# zero_board.net
KiCad netlist of a schematic drawn in EAGLE
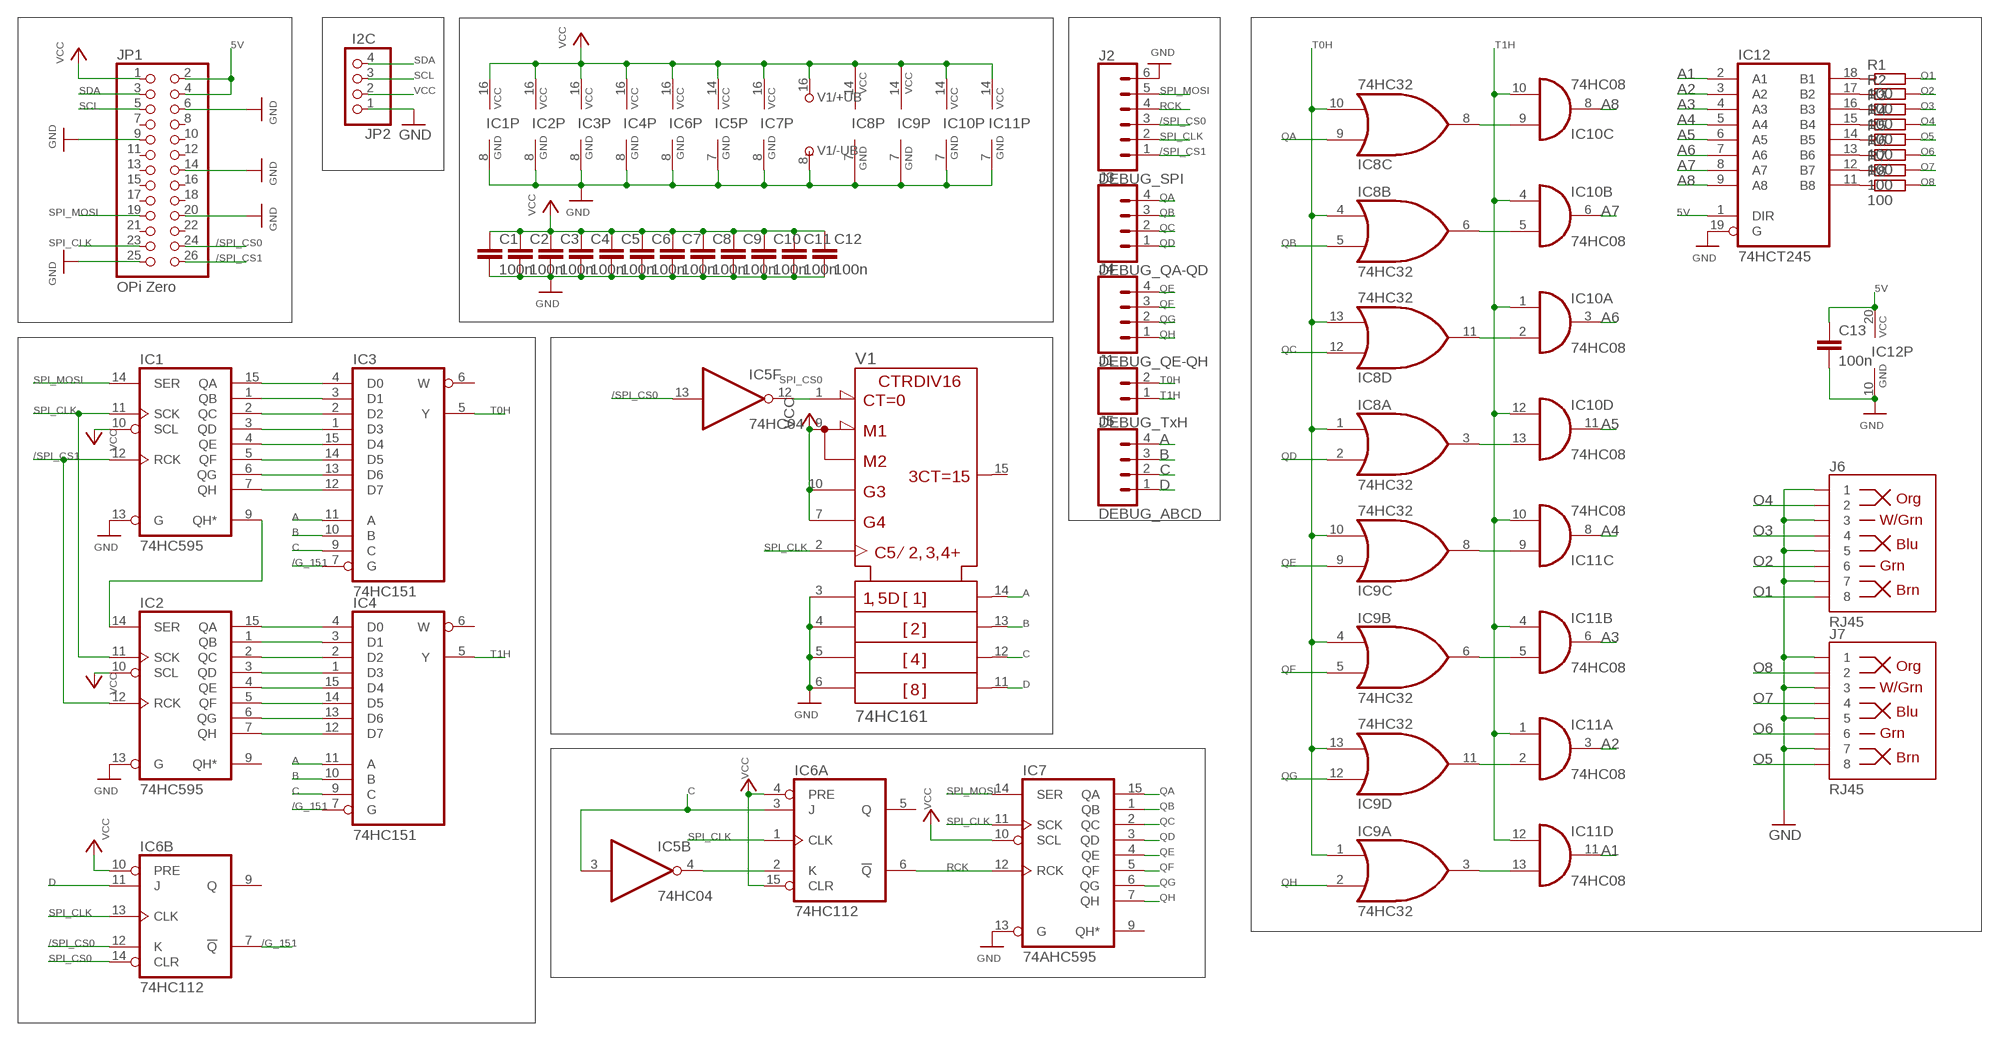
[diagram p0: schematic, sheet 1]

(export (version "E")
  (design (tool "Eeschema 10.0.6"))
  (components
    (comp (ref "C1")
      (value "100n")
      (footprint "eagle-import:C050-024X044")
      (libsource (lib "eagle-import") (part "C-EU050-024X044"))
    )
    (comp (ref "C2")
      (value "100n")
      (footprint "eagle-import:C050-024X044")
      (libsource (lib "eagle-import") (part "C-EU050-024X044"))
    )
    (comp (ref "C3")
      (value "100n")
      (footprint "eagle-import:C050-024X044")
      (libsource (lib "eagle-import") (part "C-EU050-024X044"))
    )
    (comp (ref "C4")
      (value "100n")
      (footprint "eagle-import:C050-024X044")
      (libsource (lib "eagle-import") (part "C-EU050-024X044"))
    )
    (comp (ref "C5")
      (value "100n")
      (footprint "eagle-import:C050-024X044")
      (libsource (lib "eagle-import") (part "C-EU050-024X044"))
    )
    (comp (ref "C6")
      (value "100n")
      (footprint "eagle-import:C050-024X044")
      (libsource (lib "eagle-import") (part "C-EU050-024X044"))
    )
    (comp (ref "C7")
      (value "100n")
      (footprint "eagle-import:C050-024X044")
      (libsource (lib "eagle-import") (part "C-EU050-024X044"))
    )
    (comp (ref "C8")
      (value "100n")
      (footprint "eagle-import:C050-024X044")
      (libsource (lib "eagle-import") (part "C-EU050-024X044"))
    )
    (comp (ref "C9")
      (value "100n")
      (footprint "eagle-import:C050-024X044")
      (libsource (lib "eagle-import") (part "C-EU050-024X044"))
    )
    (comp (ref "C10")
      (value "100n")
      (footprint "eagle-import:C050-024X044")
      (libsource (lib "eagle-import") (part "C-EU050-024X044"))
    )
    (comp (ref "C11")
      (value "100n")
      (footprint "eagle-import:C050-024X044")
      (libsource (lib "eagle-import") (part "C-EU050-024X044"))
    )
    (comp (ref "C12")
      (value "100n")
      (footprint "eagle-import:C050-024X044")
      (libsource (lib "eagle-import") (part "C-EU050-024X044"))
    )
    (comp (ref "C13")
      (value "100n")
      (footprint "eagle-import:C050-024X044")
      (libsource (lib "eagle-import") (part "C-EU050-024X044"))
    )
    (comp (ref "IC1")
      (value "74HC595")
      (footprint "eagle-import:DIL16")
      (libsource (lib "eagle-import") (part "74595NHC"))
    )
    (comp (ref "IC2")
      (value "74HC595")
      (footprint "eagle-import:DIL16")
      (libsource (lib "eagle-import") (part "74595NHC"))
    )
    (comp (ref "IC3")
      (value "74HC151")
      (footprint "eagle-import:DIL16")
      (libsource (lib "eagle-import") (part "74151NHC"))
    )
    (comp (ref "IC4")
      (value "74HC151")
      (footprint "eagle-import:DIL16")
      (libsource (lib "eagle-import") (part "74151NHC"))
    )
    (comp (ref "IC5")
      (value "74HC04")
      (footprint "eagle-import:DIL14")
      (libsource (lib "eagle-import") (part "7404NHC"))
    )
    (comp (ref "IC6")
      (value "74HC112")
      (footprint "eagle-import:DIL16")
      (libsource (lib "eagle-import") (part "74112NHC"))
    )
    (comp (ref "IC7")
      (value "74AHC595")
      (footprint "eagle-import:SO16")
      (libsource (lib "eagle-import") (part "74595DHC"))
    )
    (comp (ref "IC8")
      (value "74HC32")
      (footprint "eagle-import:DIL14")
      (libsource (lib "eagle-import") (part "7432NLS"))
    )
    (comp (ref "IC9")
      (value "74HC32")
      (footprint "eagle-import:DIL14")
      (libsource (lib "eagle-import") (part "7432NLS"))
    )
    (comp (ref "IC10")
      (value "74HC08")
      (footprint "eagle-import:DIL14")
      (libsource (lib "eagle-import") (part "7408NAS"))
    )
    (comp (ref "IC11")
      (value "74HC08")
      (footprint "eagle-import:DIL14")
      (libsource (lib "eagle-import") (part "7408NAS"))
    )
    (comp (ref "IC12")
      (value "74HCT245")
      (footprint "eagle-import:DIL20")
      (libsource (lib "eagle-import") (part "74245NACT"))
    )
    (comp (ref "J1")
      (value "DEBUG_TxH")
      (footprint "eagle-import:1X02")
      (libsource (lib "eagle-import") (part "CONN_02"))
    )
    (comp (ref "J2")
      (value "DEBUG_SPI")
      (footprint "eagle-import:1X06_LOCK")
      (libsource (lib "eagle-import") (part "CONN_06LOCK"))
    )
    (comp (ref "J3")
      (value "DEBUG_QA-QD")
      (footprint "eagle-import:1X04_LOCK")
      (libsource (lib "eagle-import") (part "CONN_04LOCK"))
    )
    (comp (ref "J4")
      (value "DEBUG_QE-QH")
      (footprint "eagle-import:1X04_LOCK")
      (libsource (lib "eagle-import") (part "CONN_04LOCK"))
    )
    (comp (ref "J5")
      (value "DEBUG_ABCD")
      (footprint "eagle-import:1X04_LOCK")
      (libsource (lib "eagle-import") (part "CONN_04LOCK"))
    )
    (comp (ref "J6")
      (value "RJ45")
      (footprint "eagle-import:RJ45-8")
      (libsource (lib "eagle-import") (part "RJ45-8"))
    )
    (comp (ref "J7")
      (value "RJ45")
      (footprint "eagle-import:RJ45-8")
      (libsource (lib "eagle-import") (part "RJ45-8"))
    )
    (comp (ref "JP1")
      (value "OPi Zero")
      (footprint "eagle-import:2X13")
      (libsource (lib "eagle-import") (part "PINHD-2X13"))
    )
    (comp (ref "JP2")
      (value "I2C")
      (footprint "eagle-import:1X04")
      (libsource (lib "eagle-import") (part "PINHD-1X4"))
    )
    (comp (ref "R1")
      (value "100")
      (footprint "eagle-import:0204_5")
      (libsource (lib "eagle-import") (part "R-EU_0204/5"))
    )
    (comp (ref "R2")
      (value "100")
      (footprint "eagle-import:0204_5")
      (libsource (lib "eagle-import") (part "R-EU_0204/5"))
    )
    (comp (ref "R3")
      (value "100")
      (footprint "eagle-import:0204_5")
      (libsource (lib "eagle-import") (part "R-EU_0204/5"))
    )
    (comp (ref "R4")
      (value "100")
      (footprint "eagle-import:0204_5")
      (libsource (lib "eagle-import") (part "R-EU_0204/5"))
    )
    (comp (ref "R5")
      (value "100")
      (footprint "eagle-import:0204_5")
      (libsource (lib "eagle-import") (part "R-EU_0204/5"))
    )
    (comp (ref "R6")
      (value "100")
      (footprint "eagle-import:0204_5")
      (libsource (lib "eagle-import") (part "R-EU_0204/5"))
    )
    (comp (ref "R7")
      (value "100")
      (footprint "eagle-import:0204_5")
      (libsource (lib "eagle-import") (part "R-EU_0204/5"))
    )
    (comp (ref "R8")
      (value "100")
      (footprint "eagle-import:0204_5")
      (libsource (lib "eagle-import") (part "R-EU_0204/5"))
    )
    (comp (ref "V1")
      (value "74HC161")
      (footprint "eagle-import:DIL16")
      (libsource (lib "eagle-import") (part "74161N"))
    )
  )
  (nets
    (net (code "1") (name "/5V") (class "Default")
      (node (ref "C13") (pin "1") (pinfunction "1_1") (pintype "passive"))
      (node (ref "IC12") (pin "1") (pinfunction "DIR_1") (pintype "input"))
      (node (ref "IC12") (pin "20") (pinfunction "VCC_20") (pintype "power_in"))
      (node (ref "JP1") (pin "2") (pinfunction "2_2") (pintype "passive"))
      (node (ref "JP1") (pin "4") (pinfunction "4_4") (pintype "passive"))
    )
    (net (code "2") (name "/A") (class "Default")
      (node (ref "IC3") (pin "11") (pinfunction "A_11") (pintype "input"))
      (node (ref "IC4") (pin "11") (pinfunction "A_11") (pintype "input"))
      (node (ref "J5") (pin "4") (pinfunction "4_4") (pintype "passive"))
      (node (ref "V1") (pin "14") (pinfunction "QA_14") (pintype "output"))
    )
    (net (code "3") (name "/A1") (class "Default")
      (node (ref "IC11") (pin "11") (pinfunction "O_11") (pintype "output"))
      (node (ref "IC12") (pin "2") (pinfunction "A1_2") (pintype "bidirectional"))
    )
    (net (code "4") (name "/A2") (class "Default")
      (node (ref "IC11") (pin "3") (pinfunction "O_3") (pintype "output"))
      (node (ref "IC12") (pin "3") (pinfunction "A2_3") (pintype "bidirectional"))
    )
    (net (code "5") (name "/A3") (class "Default")
      (node (ref "IC11") (pin "6") (pinfunction "O_6") (pintype "output"))
      (node (ref "IC12") (pin "4") (pinfunction "A3_4") (pintype "bidirectional"))
    )
    (net (code "6") (name "/A4") (class "Default")
      (node (ref "IC11") (pin "8") (pinfunction "O_8") (pintype "output"))
      (node (ref "IC12") (pin "5") (pinfunction "A4_5") (pintype "bidirectional"))
    )
    (net (code "7") (name "/A5") (class "Default")
      (node (ref "IC10") (pin "11") (pinfunction "O_11") (pintype "output"))
      (node (ref "IC12") (pin "6") (pinfunction "A5_6") (pintype "bidirectional"))
    )
    (net (code "8") (name "/A6") (class "Default")
      (node (ref "IC10") (pin "3") (pinfunction "O_3") (pintype "output"))
      (node (ref "IC12") (pin "7") (pinfunction "A6_7") (pintype "bidirectional"))
    )
    (net (code "9") (name "/A7") (class "Default")
      (node (ref "IC10") (pin "6") (pinfunction "O_6") (pintype "output"))
      (node (ref "IC12") (pin "8") (pinfunction "A7_8") (pintype "bidirectional"))
    )
    (net (code "10") (name "/A8") (class "Default")
      (node (ref "IC10") (pin "8") (pinfunction "O_8") (pintype "output"))
      (node (ref "IC12") (pin "9") (pinfunction "A8_9") (pintype "bidirectional"))
    )
    (net (code "11") (name "/B") (class "Default")
      (node (ref "IC3") (pin "10") (pinfunction "B_10") (pintype "input"))
      (node (ref "IC4") (pin "10") (pinfunction "B_10") (pintype "input"))
      (node (ref "J5") (pin "3") (pinfunction "3_3") (pintype "passive"))
      (node (ref "V1") (pin "13") (pinfunction "QB_13") (pintype "output"))
    )
    (net (code "12") (name "/C") (class "Default")
      (node (ref "IC3") (pin "9") (pinfunction "C_9") (pintype "input"))
      (node (ref "IC4") (pin "9") (pinfunction "C_9") (pintype "input"))
      (node (ref "IC5") (pin "3") (pinfunction "I_3") (pintype "input"))
      (node (ref "IC6") (pin "3") (pinfunction "J_3") (pintype "input"))
      (node (ref "J5") (pin "2") (pinfunction "2_2") (pintype "passive"))
      (node (ref "V1") (pin "12") (pinfunction "QC_12") (pintype "output"))
    )
    (net (code "13") (name "/D") (class "Default")
      (node (ref "IC6") (pin "11") (pinfunction "J_11") (pintype "input"))
      (node (ref "J5") (pin "1") (pinfunction "1_1") (pintype "passive"))
      (node (ref "V1") (pin "11") (pinfunction "QD_11") (pintype "output"))
    )
    (net (code "14") (name "/O1") (class "Default")
      (node (ref "J6") (pin "8") (pinfunction "8_8") (pintype "bidirectional"))
      (node (ref "R1") (pin "2") (pinfunction "2_2") (pintype "passive"))
    )
    (net (code "15") (name "/O2") (class "Default")
      (node (ref "J6") (pin "6") (pinfunction "6_6") (pintype "bidirectional"))
      (node (ref "R2") (pin "2") (pinfunction "2_2") (pintype "passive"))
    )
    (net (code "16") (name "/O3") (class "Default")
      (node (ref "J6") (pin "4") (pinfunction "4_4") (pintype "bidirectional"))
      (node (ref "R3") (pin "2") (pinfunction "2_2") (pintype "passive"))
    )
    (net (code "17") (name "/O4") (class "Default")
      (node (ref "J6") (pin "2") (pinfunction "2_2") (pintype "bidirectional"))
      (node (ref "R4") (pin "2") (pinfunction "2_2") (pintype "passive"))
    )
    (net (code "18") (name "/O5") (class "Default")
      (node (ref "J7") (pin "8") (pinfunction "8_8") (pintype "bidirectional"))
      (node (ref "R5") (pin "2") (pinfunction "2_2") (pintype "passive"))
    )
    (net (code "19") (name "/O6") (class "Default")
      (node (ref "J7") (pin "6") (pinfunction "6_6") (pintype "bidirectional"))
      (node (ref "R6") (pin "2") (pinfunction "2_2") (pintype "passive"))
    )
    (net (code "20") (name "/O7") (class "Default")
      (node (ref "J7") (pin "4") (pinfunction "4_4") (pintype "bidirectional"))
      (node (ref "R7") (pin "2") (pinfunction "2_2") (pintype "passive"))
    )
    (net (code "21") (name "/O8") (class "Default")
      (node (ref "J7") (pin "2") (pinfunction "2_2") (pintype "bidirectional"))
      (node (ref "R8") (pin "2") (pinfunction "2_2") (pintype "passive"))
    )
    (net (code "22") (name "/QA") (class "Default")
      (node (ref "IC7") (pin "15") (pinfunction "QA_15") (pintype "tri_state"))
      (node (ref "IC8") (pin "9") (pinfunction "I0_9") (pintype "input"))
      (node (ref "J3") (pin "4") (pinfunction "4_4") (pintype "passive"))
    )
    (net (code "23") (name "/QB") (class "Default")
      (node (ref "IC7") (pin "1") (pinfunction "QB_1") (pintype "tri_state"))
      (node (ref "IC8") (pin "5") (pinfunction "I1_5") (pintype "input"))
      (node (ref "J3") (pin "3") (pinfunction "3_3") (pintype "passive"))
    )
    (net (code "24") (name "/QC") (class "Default")
      (node (ref "IC7") (pin "2") (pinfunction "QC_2") (pintype "tri_state"))
      (node (ref "IC8") (pin "12") (pinfunction "I0_12") (pintype "input"))
      (node (ref "J3") (pin "2") (pinfunction "2_2") (pintype "passive"))
    )
    (net (code "25") (name "/QD") (class "Default")
      (node (ref "IC7") (pin "3") (pinfunction "QD_3") (pintype "tri_state"))
      (node (ref "IC8") (pin "2") (pinfunction "I1_2") (pintype "input"))
      (node (ref "J3") (pin "1") (pinfunction "1_1") (pintype "passive"))
    )
    (net (code "26") (name "/QE") (class "Default")
      (node (ref "IC7") (pin "4") (pinfunction "QE_4") (pintype "tri_state"))
      (node (ref "IC9") (pin "9") (pinfunction "I0_9") (pintype "input"))
      (node (ref "J4") (pin "4") (pinfunction "4_4") (pintype "passive"))
    )
    (net (code "27") (name "/QF") (class "Default")
      (node (ref "IC7") (pin "5") (pinfunction "QF_5") (pintype "tri_state"))
      (node (ref "IC9") (pin "5") (pinfunction "I1_5") (pintype "input"))
      (node (ref "J4") (pin "3") (pinfunction "3_3") (pintype "passive"))
    )
    (net (code "28") (name "/QG") (class "Default")
      (node (ref "IC7") (pin "6") (pinfunction "QG_6") (pintype "tri_state"))
      (node (ref "IC9") (pin "12") (pinfunction "I0_12") (pintype "input"))
      (node (ref "J4") (pin "2") (pinfunction "2_2") (pintype "passive"))
    )
    (net (code "29") (name "/QH") (class "Default")
      (node (ref "IC7") (pin "7") (pinfunction "QH_7") (pintype "tri_state"))
      (node (ref "IC9") (pin "2") (pinfunction "I1_2") (pintype "input"))
      (node (ref "J4") (pin "1") (pinfunction "1_1") (pintype "passive"))
    )
    (net (code "30") (name "/RCK") (class "Default")
      (node (ref "IC6") (pin "6") (pinfunction "~{Q}_6") (pintype "output"))
      (node (ref "IC7") (pin "12") (pinfunction "RCK_12") (pintype "input"))
      (node (ref "J2") (pin "4") (pinfunction "4_4") (pintype "passive"))
    )
    (net (code "31") (name "/SCL") (class "Default")
      (node (ref "JP1") (pin "5") (pinfunction "5_5") (pintype "passive"))
      (node (ref "JP2") (pin "3") (pinfunction "3_3") (pintype "passive"))
    )
    (net (code "32") (name "/SDA") (class "Default")
      (node (ref "JP1") (pin "3") (pinfunction "3_3") (pintype "passive"))
      (node (ref "JP2") (pin "4") (pinfunction "4_4") (pintype "passive"))
    )
    (net (code "33") (name "/SPI_CLK") (class "Default")
      (node (ref "IC1") (pin "11") (pinfunction "SCK_11") (pintype "input"))
      (node (ref "IC2") (pin "11") (pinfunction "SCK_11") (pintype "input"))
      (node (ref "IC6") (pin "1") (pinfunction "CLK_1") (pintype "input"))
      (node (ref "IC6") (pin "13") (pinfunction "CLK_13") (pintype "input"))
      (node (ref "IC7") (pin "11") (pinfunction "SCK_11") (pintype "input"))
      (node (ref "J2") (pin "2") (pinfunction "2_2") (pintype "passive"))
      (node (ref "JP1") (pin "23") (pinfunction "23_23") (pintype "passive"))
      (node (ref "V1") (pin "2") (pinfunction "CLK_2") (pintype "input"))
    )
    (net (code "34") (name "/SPI_CS0") (class "Default")
      (node (ref "IC5") (pin "12") (pinfunction "O_12") (pintype "output"))
      (node (ref "IC6") (pin "14") (pinfunction "CLR_14") (pintype "input"))
      (node (ref "V1") (pin "1") (pinfunction "~{CLR}_1") (pintype "input"))
    )
    (net (code "35") (name "/SPI_MOSI") (class "Default")
      (node (ref "IC1") (pin "14") (pinfunction "SER_14") (pintype "input"))
      (node (ref "IC7") (pin "14") (pinfunction "SER_14") (pintype "input"))
      (node (ref "J2") (pin "5") (pinfunction "5_5") (pintype "passive"))
      (node (ref "JP1") (pin "19") (pinfunction "19_19") (pintype "passive"))
    )
    (net (code "36") (name "/T0H") (class "Default")
      (node (ref "IC3") (pin "5") (pinfunction "Y_5") (pintype "output"))
      (node (ref "IC8") (pin "1") (pinfunction "I0_1") (pintype "input"))
      (node (ref "IC8") (pin "10") (pinfunction "I1_10") (pintype "input"))
      (node (ref "IC8") (pin "13") (pinfunction "I1_13") (pintype "input"))
      (node (ref "IC8") (pin "4") (pinfunction "I0_4") (pintype "input"))
      (node (ref "IC9") (pin "1") (pinfunction "I0_1") (pintype "input"))
      (node (ref "IC9") (pin "10") (pinfunction "I1_10") (pintype "input"))
      (node (ref "IC9") (pin "13") (pinfunction "I1_13") (pintype "input"))
      (node (ref "IC9") (pin "4") (pinfunction "I0_4") (pintype "input"))
      (node (ref "J1") (pin "2") (pinfunction "2_2") (pintype "passive"))
    )
    (net (code "37") (name "/T1H") (class "Default")
      (node (ref "IC10") (pin "1") (pinfunction "I0_1") (pintype "input"))
      (node (ref "IC10") (pin "10") (pinfunction "I1_10") (pintype "input"))
      (node (ref "IC10") (pin "12") (pinfunction "I0_12") (pintype "input"))
      (node (ref "IC10") (pin "4") (pinfunction "I0_4") (pintype "input"))
      (node (ref "IC11") (pin "1") (pinfunction "I0_1") (pintype "input"))
      (node (ref "IC11") (pin "10") (pinfunction "I1_10") (pintype "input"))
      (node (ref "IC11") (pin "12") (pinfunction "I0_12") (pintype "input"))
      (node (ref "IC11") (pin "4") (pinfunction "I0_4") (pintype "input"))
      (node (ref "IC4") (pin "5") (pinfunction "Y_5") (pintype "output"))
      (node (ref "J1") (pin "1") (pinfunction "1_1") (pintype "passive"))
    )
    (net (code "38") (name "/{slash}G_151") (class "Default")
      (node (ref "IC3") (pin "7") (pinfunction "G_7") (pintype "input"))
      (node (ref "IC4") (pin "7") (pinfunction "G_7") (pintype "input"))
      (node (ref "IC6") (pin "7") (pinfunction "~{Q}_7") (pintype "output"))
    )
    (net (code "39") (name "/{slash}SPI_CS0") (class "Default")
      (node (ref "IC5") (pin "13") (pinfunction "I_13") (pintype "input"))
      (node (ref "IC6") (pin "12") (pinfunction "K_12") (pintype "input"))
      (node (ref "J2") (pin "3") (pinfunction "3_3") (pintype "passive"))
      (node (ref "JP1") (pin "24") (pinfunction "24_24") (pintype "passive"))
    )
    (net (code "40") (name "/{slash}SPI_CS1") (class "Default")
      (node (ref "IC1") (pin "12") (pinfunction "RCK_12") (pintype "input"))
      (node (ref "IC2") (pin "12") (pinfunction "RCK_12") (pintype "input"))
      (node (ref "J2") (pin "1") (pinfunction "1_1") (pintype "passive"))
      (node (ref "JP1") (pin "26") (pinfunction "26_26") (pintype "passive"))
    )
    (net (code "41") (name "GND") (class "Default")
      (node (ref "C1") (pin "2") (pinfunction "2_2") (pintype "passive"))
      (node (ref "C10") (pin "2") (pinfunction "2_2") (pintype "passive"))
      (node (ref "C11") (pin "2") (pinfunction "2_2") (pintype "passive"))
      (node (ref "C12") (pin "2") (pinfunction "2_2") (pintype "passive"))
      (node (ref "C13") (pin "2") (pinfunction "2_2") (pintype "passive"))
      (node (ref "C2") (pin "2") (pinfunction "2_2") (pintype "passive"))
      (node (ref "C3") (pin "2") (pinfunction "2_2") (pintype "passive"))
      (node (ref "C4") (pin "2") (pinfunction "2_2") (pintype "passive"))
      (node (ref "C5") (pin "2") (pinfunction "2_2") (pintype "passive"))
      (node (ref "C6") (pin "2") (pinfunction "2_2") (pintype "passive"))
      (node (ref "C7") (pin "2") (pinfunction "2_2") (pintype "passive"))
      (node (ref "C8") (pin "2") (pinfunction "2_2") (pintype "passive"))
      (node (ref "C9") (pin "2") (pinfunction "2_2") (pintype "passive"))
      (node (ref "IC1") (pin "13") (pinfunction "G_13") (pintype "input"))
      (node (ref "IC1") (pin "8") (pinfunction "GND_8") (pintype "power_in"))
      (node (ref "IC10") (pin "7") (pinfunction "GND_7") (pintype "power_in"))
      (node (ref "IC11") (pin "7") (pinfunction "GND_7") (pintype "power_in"))
      (node (ref "IC12") (pin "10") (pinfunction "GND_10") (pintype "power_in"))
      (node (ref "IC12") (pin "19") (pinfunction "G_19") (pintype "input"))
      (node (ref "IC2") (pin "13") (pinfunction "G_13") (pintype "input"))
      (node (ref "IC2") (pin "8") (pinfunction "GND_8") (pintype "power_in"))
      (node (ref "IC3") (pin "8") (pinfunction "GND_8") (pintype "power_in"))
      (node (ref "IC4") (pin "8") (pinfunction "GND_8") (pintype "power_in"))
      (node (ref "IC5") (pin "7") (pinfunction "GND_7") (pintype "power_in"))
      (node (ref "IC6") (pin "8") (pinfunction "GND_8") (pintype "power_in"))
      (node (ref "IC7") (pin "13") (pinfunction "G_13") (pintype "input"))
      (node (ref "IC7") (pin "8") (pinfunction "GND_8") (pintype "power_in"))
      (node (ref "IC8") (pin "7") (pinfunction "GND_7") (pintype "power_in"))
      (node (ref "IC9") (pin "7") (pinfunction "GND_7") (pintype "power_in"))
      (node (ref "J2") (pin "6") (pinfunction "6_6") (pintype "passive"))
      (node (ref "J6") (pin "1") (pinfunction "1_1") (pintype "bidirectional"))
      (node (ref "J6") (pin "3") (pinfunction "3_3") (pintype "bidirectional"))
      (node (ref "J6") (pin "5") (pinfunction "5_5") (pintype "bidirectional"))
      (node (ref "J6") (pin "7") (pinfunction "7_7") (pintype "bidirectional"))
      (node (ref "J7") (pin "1") (pinfunction "1_1") (pintype "bidirectional"))
      (node (ref "J7") (pin "3") (pinfunction "3_3") (pintype "bidirectional"))
      (node (ref "J7") (pin "5") (pinfunction "5_5") (pintype "bidirectional"))
      (node (ref "J7") (pin "7") (pinfunction "7_7") (pintype "bidirectional"))
      (node (ref "JP1") (pin "14") (pinfunction "14_14") (pintype "passive"))
      (node (ref "JP1") (pin "20") (pinfunction "20_20") (pintype "passive"))
      (node (ref "JP1") (pin "25") (pinfunction "25_25") (pintype "passive"))
      (node (ref "JP1") (pin "6") (pinfunction "6_6") (pintype "passive"))
      (node (ref "JP1") (pin "9") (pinfunction "9_9") (pintype "passive"))
      (node (ref "JP2") (pin "1") (pinfunction "1_1") (pintype "passive"))
      (node (ref "V1") (pin "3") (pinfunction "A_3") (pintype "input"))
      (node (ref "V1") (pin "4") (pinfunction "B_4") (pintype "input"))
      (node (ref "V1") (pin "5") (pinfunction "C_5") (pintype "input"))
      (node (ref "V1") (pin "6") (pinfunction "D_6") (pintype "input"))
      (node (ref "V1") (pin "8") (pinfunction "-UB_8") (pintype "power_in"))
    )
    (net (code "42") (name "Net-(IC1A-QA)") (class "Default")
      (node (ref "IC1") (pin "15") (pinfunction "QA_15") (pintype "tri_state"))
      (node (ref "IC3") (pin "4") (pinfunction "D0_4") (pintype "input"))
    )
    (net (code "43") (name "Net-(IC1A-QB)") (class "Default")
      (node (ref "IC1") (pin "1") (pinfunction "QB_1") (pintype "tri_state"))
      (node (ref "IC3") (pin "3") (pinfunction "D1_3") (pintype "input"))
    )
    (net (code "44") (name "Net-(IC1A-QC)") (class "Default")
      (node (ref "IC1") (pin "2") (pinfunction "QC_2") (pintype "tri_state"))
      (node (ref "IC3") (pin "2") (pinfunction "D2_2") (pintype "input"))
    )
    (net (code "45") (name "Net-(IC1A-QD)") (class "Default")
      (node (ref "IC1") (pin "3") (pinfunction "QD_3") (pintype "tri_state"))
      (node (ref "IC3") (pin "1") (pinfunction "D3_1") (pintype "input"))
    )
    (net (code "46") (name "Net-(IC1A-QE)") (class "Default")
      (node (ref "IC1") (pin "4") (pinfunction "QE_4") (pintype "tri_state"))
      (node (ref "IC3") (pin "15") (pinfunction "D4_15") (pintype "input"))
    )
    (net (code "47") (name "Net-(IC1A-QF)") (class "Default")
      (node (ref "IC1") (pin "5") (pinfunction "QF_5") (pintype "tri_state"))
      (node (ref "IC3") (pin "14") (pinfunction "D5_14") (pintype "input"))
    )
    (net (code "48") (name "Net-(IC1A-QG)") (class "Default")
      (node (ref "IC1") (pin "6") (pinfunction "QG_6") (pintype "tri_state"))
      (node (ref "IC3") (pin "13") (pinfunction "D6_13") (pintype "input"))
    )
    (net (code "49") (name "Net-(IC1A-QH)") (class "Default")
      (node (ref "IC1") (pin "7") (pinfunction "QH_7") (pintype "tri_state"))
      (node (ref "IC3") (pin "12") (pinfunction "D7_12") (pintype "input"))
    )
    (net (code "50") (name "Net-(IC1A-QH*)") (class "Default")
      (node (ref "IC1") (pin "9") (pinfunction "QH*_9") (pintype "tri_state"))
      (node (ref "IC2") (pin "14") (pinfunction "SER_14") (pintype "input"))
    )
    (net (code "51") (name "Net-(IC2A-QA)") (class "Default")
      (node (ref "IC2") (pin "15") (pinfunction "QA_15") (pintype "tri_state"))
      (node (ref "IC4") (pin "4") (pinfunction "D0_4") (pintype "input"))
    )
    (net (code "52") (name "Net-(IC2A-QB)") (class "Default")
      (node (ref "IC2") (pin "1") (pinfunction "QB_1") (pintype "tri_state"))
      (node (ref "IC4") (pin "3") (pinfunction "D1_3") (pintype "input"))
    )
    (net (code "53") (name "Net-(IC2A-QC)") (class "Default")
      (node (ref "IC2") (pin "2") (pinfunction "QC_2") (pintype "tri_state"))
      (node (ref "IC4") (pin "2") (pinfunction "D2_2") (pintype "input"))
    )
    (net (code "54") (name "Net-(IC2A-QD)") (class "Default")
      (node (ref "IC2") (pin "3") (pinfunction "QD_3") (pintype "tri_state"))
      (node (ref "IC4") (pin "1") (pinfunction "D3_1") (pintype "input"))
    )
    (net (code "55") (name "Net-(IC2A-QE)") (class "Default")
      (node (ref "IC2") (pin "4") (pinfunction "QE_4") (pintype "tri_state"))
      (node (ref "IC4") (pin "15") (pinfunction "D4_15") (pintype "input"))
    )
    (net (code "56") (name "Net-(IC2A-QF)") (class "Default")
      (node (ref "IC2") (pin "5") (pinfunction "QF_5") (pintype "tri_state"))
      (node (ref "IC4") (pin "14") (pinfunction "D5_14") (pintype "input"))
    )
    (net (code "57") (name "Net-(IC2A-QG)") (class "Default")
      (node (ref "IC2") (pin "6") (pinfunction "QG_6") (pintype "tri_state"))
      (node (ref "IC4") (pin "13") (pinfunction "D6_13") (pintype "input"))
    )
    (net (code "58") (name "Net-(IC2A-QH)") (class "Default")
      (node (ref "IC2") (pin "7") (pinfunction "QH_7") (pintype "tri_state"))
      (node (ref "IC4") (pin "12") (pinfunction "D7_12") (pintype "input"))
    )
    (net (code "59") (name "Net-(IC5B-O)") (class "Default")
      (node (ref "IC5") (pin "4") (pinfunction "O_4") (pintype "output"))
      (node (ref "IC6") (pin "2") (pinfunction "K_2") (pintype "input"))
    )
    (net (code "60") (name "Net-(IC10A-I1)") (class "Default")
      (node (ref "IC10") (pin "2") (pinfunction "I1_2") (pintype "input"))
      (node (ref "IC8") (pin "11") (pinfunction "O_11") (pintype "output"))
    )
    (net (code "61") (name "Net-(IC10B-I1)") (class "Default")
      (node (ref "IC10") (pin "5") (pinfunction "I1_5") (pintype "input"))
      (node (ref "IC8") (pin "6") (pinfunction "O_6") (pintype "output"))
    )
    (net (code "62") (name "Net-(IC10C-I0)") (class "Default")
      (node (ref "IC10") (pin "9") (pinfunction "I0_9") (pintype "input"))
      (node (ref "IC8") (pin "8") (pinfunction "O_8") (pintype "output"))
    )
    (net (code "63") (name "Net-(IC10D-I1)") (class "Default")
      (node (ref "IC10") (pin "13") (pinfunction "I1_13") (pintype "input"))
      (node (ref "IC8") (pin "3") (pinfunction "O_3") (pintype "output"))
    )
    (net (code "64") (name "Net-(IC11A-I1)") (class "Default")
      (node (ref "IC11") (pin "2") (pinfunction "I1_2") (pintype "input"))
      (node (ref "IC9") (pin "11") (pinfunction "O_11") (pintype "output"))
    )
    (net (code "65") (name "Net-(IC11B-I1)") (class "Default")
      (node (ref "IC11") (pin "5") (pinfunction "I1_5") (pintype "input"))
      (node (ref "IC9") (pin "6") (pinfunction "O_6") (pintype "output"))
    )
    (net (code "66") (name "Net-(IC11C-I0)") (class "Default")
      (node (ref "IC11") (pin "9") (pinfunction "I0_9") (pintype "input"))
      (node (ref "IC9") (pin "8") (pinfunction "O_8") (pintype "output"))
    )
    (net (code "67") (name "Net-(IC11D-I1)") (class "Default")
      (node (ref "IC11") (pin "13") (pinfunction "I1_13") (pintype "input"))
      (node (ref "IC9") (pin "3") (pinfunction "O_3") (pintype "output"))
    )
    (net (code "68") (name "Net-(IC12A-B1)") (class "Default")
      (node (ref "IC12") (pin "18") (pinfunction "B1_18") (pintype "bidirectional"))
      (node (ref "R1") (pin "1") (pinfunction "1_1") (pintype "passive"))
    )
    (net (code "69") (name "Net-(IC12A-B2)") (class "Default")
      (node (ref "IC12") (pin "17") (pinfunction "B2_17") (pintype "bidirectional"))
      (node (ref "R2") (pin "1") (pinfunction "1_1") (pintype "passive"))
    )
    (net (code "70") (name "Net-(IC12A-B3)") (class "Default")
      (node (ref "IC12") (pin "16") (pinfunction "B3_16") (pintype "bidirectional"))
      (node (ref "R3") (pin "1") (pinfunction "1_1") (pintype "passive"))
    )
    (net (code "71") (name "Net-(IC12A-B4)") (class "Default")
      (node (ref "IC12") (pin "15") (pinfunction "B4_15") (pintype "bidirectional"))
      (node (ref "R4") (pin "1") (pinfunction "1_1") (pintype "passive"))
    )
    (net (code "72") (name "Net-(IC12A-B5)") (class "Default")
      (node (ref "IC12") (pin "14") (pinfunction "B5_14") (pintype "bidirectional"))
      (node (ref "R5") (pin "1") (pinfunction "1_1") (pintype "passive"))
    )
    (net (code "73") (name "Net-(IC12A-B6)") (class "Default")
      (node (ref "IC12") (pin "13") (pinfunction "B6_13") (pintype "bidirectional"))
      (node (ref "R6") (pin "1") (pinfunction "1_1") (pintype "passive"))
    )
    (net (code "74") (name "Net-(IC12A-B7)") (class "Default")
      (node (ref "IC12") (pin "12") (pinfunction "B7_12") (pintype "bidirectional"))
      (node (ref "R7") (pin "1") (pinfunction "1_1") (pintype "passive"))
    )
    (net (code "75") (name "Net-(IC12A-B8)") (class "Default")
      (node (ref "IC12") (pin "11") (pinfunction "B8_11") (pintype "bidirectional"))
      (node (ref "R8") (pin "1") (pinfunction "1_1") (pintype "passive"))
    )
    (net (code "76") (name "VCC") (class "Default")
      (node (ref "C1") (pin "1") (pinfunction "1_1") (pintype "passive"))
      (node (ref "C10") (pin "1") (pinfunction "1_1") (pintype "passive"))
      (node (ref "C11") (pin "1") (pinfunction "1_1") (pintype "passive"))
      (node (ref "C12") (pin "1") (pinfunction "1_1") (pintype "passive"))
      (node (ref "C2") (pin "1") (pinfunction "1_1") (pintype "passive"))
      (node (ref "C3") (pin "1") (pinfunction "1_1") (pintype "passive"))
      (node (ref "C4") (pin "1") (pinfunction "1_1") (pintype "passive"))
      (node (ref "C5") (pin "1") (pinfunction "1_1") (pintype "passive"))
      (node (ref "C6") (pin "1") (pinfunction "1_1") (pintype "passive"))
      (node (ref "C7") (pin "1") (pinfunction "1_1") (pintype "passive"))
      (node (ref "C8") (pin "1") (pinfunction "1_1") (pintype "passive"))
      (node (ref "C9") (pin "1") (pinfunction "1_1") (pintype "passive"))
      (node (ref "IC1") (pin "10") (pinfunction "SCL_10") (pintype "input"))
      (node (ref "IC1") (pin "16") (pinfunction "VCC_16") (pintype "power_in"))
      (node (ref "IC10") (pin "14") (pinfunction "VCC_14") (pintype "power_in"))
      (node (ref "IC11") (pin "14") (pinfunction "VCC_14") (pintype "power_in"))
      (node (ref "IC2") (pin "10") (pinfunction "SCL_10") (pintype "input"))
      (node (ref "IC2") (pin "16") (pinfunction "VCC_16") (pintype "power_in"))
      (node (ref "IC3") (pin "16") (pinfunction "VCC_16") (pintype "power_in"))
      (node (ref "IC4") (pin "16") (pinfunction "VCC_16") (pintype "power_in"))
      (node (ref "IC5") (pin "14") (pinfunction "VCC_14") (pintype "power_in"))
      (node (ref "IC6") (pin "10") (pinfunction "PRE_10") (pintype "input"))
      (node (ref "IC6") (pin "15") (pinfunction "CLR_15") (pintype "input"))
      (node (ref "IC6") (pin "16") (pinfunction "VCC_16") (pintype "power_in"))
      (node (ref "IC6") (pin "4") (pinfunction "PRE_4") (pintype "input"))
      (node (ref "IC7") (pin "10") (pinfunction "SCL_10") (pintype "input"))
      (node (ref "IC7") (pin "16") (pinfunction "VCC_16") (pintype "power_in"))
      (node (ref "IC8") (pin "14") (pinfunction "VCC_14") (pintype "power_in"))
      (node (ref "IC9") (pin "14") (pinfunction "VCC_14") (pintype "power_in"))
      (node (ref "JP1") (pin "1") (pinfunction "1_1") (pintype "passive"))
      (node (ref "JP2") (pin "2") (pinfunction "2_2") (pintype "passive"))
      (node (ref "V1") (pin "10") (pinfunction "ENT_10") (pintype "input"))
      (node (ref "V1") (pin "16") (pinfunction "+UB_16") (pintype "power_in"))
      (node (ref "V1") (pin "7") (pinfunction "ENP_7") (pintype "input"))
      (node (ref "V1") (pin "9") (pinfunction "~{LOAD}_9") (pintype "input"))
    )
    (net (code "77") (name "unconnected-(IC2A-QH*-Pad9)") (class "Default")
      (node (ref "IC2") (pin "9") (pinfunction "QH*_9") (pintype "tri_state"))
    )
    (net (code "78") (name "unconnected-(IC3A-W-Pad6)") (class "Default")
      (node (ref "IC3") (pin "6") (pinfunction "W_6") (pintype "output"))
    )
    (net (code "79") (name "unconnected-(IC4A-W-Pad6)") (class "Default")
      (node (ref "IC4") (pin "6") (pinfunction "W_6") (pintype "output"))
    )
    (net (code "80") (name "unconnected-(IC6A-Q-Pad5)") (class "Default")
      (node (ref "IC6") (pin "5") (pinfunction "Q_5") (pintype "output"))
    )
    (net (code "81") (name "unconnected-(IC6B-Q-Pad9)") (class "Default")
      (node (ref "IC6") (pin "9") (pinfunction "Q_9") (pintype "output"))
    )
    (net (code "82") (name "unconnected-(IC7A-QH*-Pad9)") (class "Default")
      (node (ref "IC7") (pin "9") (pinfunction "QH*_9") (pintype "tri_state"))
    )
    (net (code "83") (name "unconnected-(JP1-Pad7)") (class "Default")
      (node (ref "JP1") (pin "7") (pinfunction "7_7") (pintype "passive"))
    )
    (net (code "84") (name "unconnected-(JP1-Pad8)") (class "Default")
      (node (ref "JP1") (pin "8") (pinfunction "8_8") (pintype "passive"))
    )
    (net (code "85") (name "unconnected-(JP1-Pad10)") (class "Default")
      (node (ref "JP1") (pin "10") (pinfunction "10_10") (pintype "passive"))
    )
    (net (code "86") (name "unconnected-(JP1-Pad11)") (class "Default")
      (node (ref "JP1") (pin "11") (pinfunction "11_11") (pintype "passive"))
    )
    (net (code "87") (name "unconnected-(JP1-Pad12)") (class "Default")
      (node (ref "JP1") (pin "12") (pinfunction "12_12") (pintype "passive"))
    )
    (net (code "88") (name "unconnected-(JP1-Pad13)") (class "Default")
      (node (ref "JP1") (pin "13") (pinfunction "13_13") (pintype "passive"))
    )
    (net (code "89") (name "unconnected-(JP1-Pad15)") (class "Default")
      (node (ref "JP1") (pin "15") (pinfunction "15_15") (pintype "passive"))
    )
    (net (code "90") (name "unconnected-(JP1-Pad16)") (class "Default")
      (node (ref "JP1") (pin "16") (pinfunction "16_16") (pintype "passive"))
    )
    (net (code "91") (name "unconnected-(JP1-Pad17)") (class "Default")
      (node (ref "JP1") (pin "17") (pinfunction "17_17") (pintype "passive"))
    )
    (net (code "92") (name "unconnected-(JP1-Pad18)") (class "Default")
      (node (ref "JP1") (pin "18") (pinfunction "18_18") (pintype "passive"))
    )
    (net (code "93") (name "unconnected-(JP1-Pad21)") (class "Default")
      (node (ref "JP1") (pin "21") (pinfunction "21_21") (pintype "passive"))
    )
    (net (code "94") (name "unconnected-(JP1-Pad22)") (class "Default")
      (node (ref "JP1") (pin "22") (pinfunction "22_22") (pintype "passive"))
    )
    (net (code "95") (name "unconnected-(V1C-RCO-Pad15)") (class "Default")
      (node (ref "V1") (pin "15") (pinfunction "RCO_15") (pintype "output"))
    )
  )
)
